# MT29_-_2GBiT_Parallel.net
KiCad netlist of a schematic drawn in Altium Designer
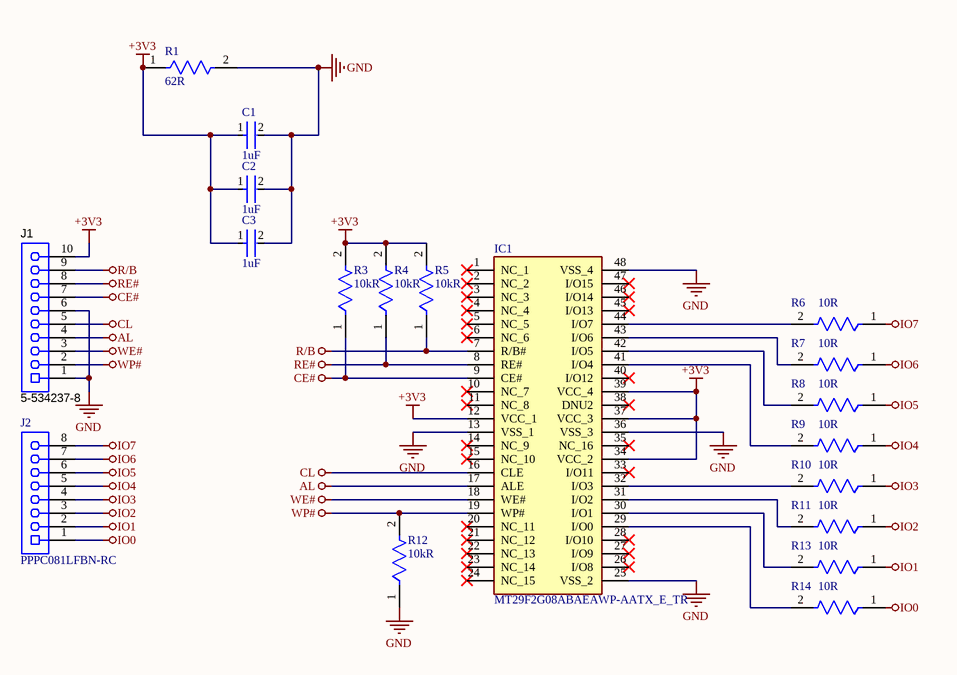
[diagram p0: MT29 - 2GBiT Parallel.SchDoc]

(export (version "E")
  (design (tool "Eeschema 10.0.6"))
  (components
    (comp (ref "C1")
      (value "1uF")
      (footprint "FP-GCM188-0_1-IPC_B")
      (description "Ceramic Capacitor for Automotive 1uF  ±10% 16VDC X7R 0603 Paper T/R")
      (fields (field (name "VOLTAGE") "16V") (field (name "TOLERANCE") "10%"))
      (libsource (lib "Altium Content Vault") (part "02cd4be3c70576c341d710602a673aa"))
    )
    (comp (ref "C2")
      (value "1uF")
      (footprint "FP-GCM188-0_1-IPC_B")
      (description "Ceramic Capacitor for Automotive 1uF  ±10% 16VDC X7R 0603 Paper T/R")
      (fields (field (name "VOLTAGE") "16V") (field (name "TOLERANCE") "10%"))
      (libsource (lib "Altium Content Vault") (part "02cd4be3c70576c341d710602a673aa"))
    )
    (comp (ref "C3")
      (value "1uF")
      (footprint "FP-GCM188-0_1-IPC_B")
      (description "Ceramic Capacitor for Automotive 1uF  ±10% 16VDC X7R 0603 Paper T/R")
      (fields (field (name "VOLTAGE") "16V") (field (name "TOLERANCE") "10%"))
      (libsource (lib "Altium Content Vault") (part "02cd4be3c70576c341d710602a673aa"))
    )
    (comp (ref "IC1")
      (value "MT29F2G08ABAEAWP-AATX_E_TR")
      (footprint "SamacSys:SOP50P2000X120-48N")
      (description "Integrated Circuit")
      (fields
        (field (name "MANUFACTURER_PART_NUMBER") "MT29F2G08ABAEAWP-AATX:E TR")
        (field (name "MOUSER PART NUMBER") "340-278557-REEL")
      )
      (libsource (lib "SamacSys") (part "MT29F2G08ABAEAWP-AATX_E_TR"))
    )
    (comp (ref "J1")
      (value "5-534237-8")
      (footprint "TECO-5-534237-8_V")
      (fields (field (name "MANUFACTURER") "TE Connectivity"))
      (libsource (lib "CubeSat Team") (part "CN-1P-F-R10"))
    )
    (comp (ref "J2")
      (value "PPPC081LFBN-RC")
      (footprint "SLIN-PPPC081LFBN-RC_V")
      (fields (field (name "MANUFACTURER") "Sullins"))
      (libsource (lib "CubeSat Team") (part "CN-1P-F-R8"))
    )
    (comp (ref "R1")
      (value "62R")
      (footprint "FP-AC0603-IPC_A")
      (description "RES 62Ω 1.00% 0.1W 0603")
      (fields (field (name "TOLERANCE") "1%"))
      (libsource (lib "Altium Content Vault") (part "1029c3af85768c4190bb7ad29bc67b5"))
    )
    (comp (ref "R3")
      (value "10kR")
      (footprint "FP-AC0603-IPC_B")
      (description "RES 910KΩ 1.00% 0.1W 0603")
      (fields (field (name "TOLERANCE") "1%"))
      (libsource (lib "Altium Content Vault") (part "1029c3af85768c4190bb7ad29bc67b5"))
    )
    (comp (ref "R4")
      (value "10kR")
      (footprint "FP-AC0603-IPC_B")
      (description "RES 910KΩ 1.00% 0.1W 0603")
      (fields (field (name "TOLERANCE") "1%"))
      (libsource (lib "Altium Content Vault") (part "1029c3af85768c4190bb7ad29bc67b5"))
    )
    (comp (ref "R5")
      (value "10kR")
      (footprint "FP-AC0603-IPC_B")
      (description "RES 910KΩ 1.00% 0.1W 0603")
      (fields (field (name "TOLERANCE") "1%"))
      (libsource (lib "Altium Content Vault") (part "1029c3af85768c4190bb7ad29bc67b5"))
    )
    (comp (ref "R6")
      (value "10R")
      (footprint "FP-AC0603-MFG")
      (description "RES 10Ω 1.00% 0.1W 0603")
      (fields (field (name "TOLERANCE") "1%"))
      (libsource (lib "Altium Content Vault") (part "1029c3af85768c4190bb7ad29bc67b5"))
    )
    (comp (ref "R7")
      (value "10R")
      (footprint "FP-AC0603-MFG")
      (description "RES 10Ω 1.00% 0.1W 0603")
      (fields (field (name "TOLERANCE") "1%"))
      (libsource (lib "Altium Content Vault") (part "1029c3af85768c4190bb7ad29bc67b5"))
    )
    (comp (ref "R8")
      (value "10R")
      (footprint "FP-AC0603-MFG")
      (description "RES 10Ω 1.00% 0.1W 0603")
      (fields (field (name "TOLERANCE") "1%"))
      (libsource (lib "Altium Content Vault") (part "1029c3af85768c4190bb7ad29bc67b5"))
    )
    (comp (ref "R9")
      (value "10R")
      (footprint "FP-AC0603-MFG")
      (description "RES 10Ω 1.00% 0.1W 0603")
      (fields (field (name "TOLERANCE") "1%"))
      (libsource (lib "Altium Content Vault") (part "1029c3af85768c4190bb7ad29bc67b5"))
    )
    (comp (ref "R10")
      (value "10R")
      (footprint "FP-AC0603-MFG")
      (description "RES 10Ω 1.00% 0.1W 0603")
      (fields (field (name "TOLERANCE") "1%"))
      (libsource (lib "Altium Content Vault") (part "1029c3af85768c4190bb7ad29bc67b5"))
    )
    (comp (ref "R11")
      (value "10R")
      (footprint "FP-AC0603-MFG")
      (description "RES 10Ω 1.00% 0.1W 0603")
      (fields (field (name "TOLERANCE") "1%"))
      (libsource (lib "Altium Content Vault") (part "1029c3af85768c4190bb7ad29bc67b5"))
    )
    (comp (ref "R12")
      (value "10kR")
      (footprint "FP-AC0603-IPC_B")
      (description "RES 910KΩ 1.00% 0.1W 0603")
      (fields (field (name "TOLERANCE") "1%"))
      (libsource (lib "Altium Content Vault") (part "1029c3af85768c4190bb7ad29bc67b5"))
    )
    (comp (ref "R13")
      (value "10R")
      (footprint "FP-AC0603-MFG")
      (description "RES 10Ω 1.00% 0.1W 0603")
      (fields (field (name "TOLERANCE") "1%"))
      (libsource (lib "Altium Content Vault") (part "1029c3af85768c4190bb7ad29bc67b5"))
    )
    (comp (ref "R14")
      (value "10R")
      (footprint "FP-AC0603-MFG")
      (description "RES 10Ω 1.00% 0.1W 0603")
      (fields (field (name "TOLERANCE") "1%"))
      (libsource (lib "Altium Content Vault") (part "1029c3af85768c4190bb7ad29bc67b5"))
    )
  )
  (nets
    (net (code "1") (name "+3V3") (class "Default")
      (node (ref "C1") (pin "1") (pinfunction "1_1") (pintype "passive"))
      (node (ref "C2") (pin "1") (pinfunction "1_1") (pintype "passive"))
      (node (ref "C3") (pin "1") (pinfunction "1_1") (pintype "passive"))
      (node (ref "IC1") (pin "12") (pinfunction "VCC_1_12") (pintype "passive"))
      (node (ref "IC1") (pin "34") (pinfunction "VCC_2_34") (pintype "passive"))
      (node (ref "IC1") (pin "37") (pinfunction "VCC_3_37") (pintype "passive"))
      (node (ref "IC1") (pin "39") (pinfunction "VCC_4_39") (pintype "passive"))
      (node (ref "J1") (pin "10") (pinfunction "10_10") (pintype "passive"))
      (node (ref "R1") (pin "1") (pinfunction "1_1") (pintype "passive"))
      (node (ref "R3") (pin "2") (pinfunction "2_2") (pintype "passive"))
      (node (ref "R4") (pin "2") (pinfunction "2_2") (pintype "passive"))
      (node (ref "R5") (pin "2") (pinfunction "2_2") (pintype "passive"))
    )
    (net (code "2") (name "AL") (class "Default")
      (node (ref "IC1") (pin "17") (pinfunction "ALE_17") (pintype "passive"))
      (node (ref "J1") (pin "4") (pinfunction "4_4") (pintype "passive"))
    )
    (net (code "3") (name "CE#") (class "Default")
      (node (ref "IC1") (pin "9") (pinfunction "CE#_9") (pintype "passive"))
      (node (ref "J1") (pin "7") (pinfunction "7_7") (pintype "passive"))
      (node (ref "R3") (pin "1") (pinfunction "1_1") (pintype "passive"))
    )
    (net (code "4") (name "CL") (class "Default")
      (node (ref "IC1") (pin "16") (pinfunction "CLE_16") (pintype "passive"))
      (node (ref "J1") (pin "5") (pinfunction "5_5") (pintype "passive"))
    )
    (net (code "5") (name "GND") (class "Default")
      (node (ref "C1") (pin "2") (pinfunction "2_2") (pintype "passive"))
      (node (ref "C2") (pin "2") (pinfunction "2_2") (pintype "passive"))
      (node (ref "C3") (pin "2") (pinfunction "2_2") (pintype "passive"))
      (node (ref "IC1") (pin "13") (pinfunction "VSS_1_13") (pintype "passive"))
      (node (ref "IC1") (pin "25") (pinfunction "VSS_2_25") (pintype "passive"))
      (node (ref "IC1") (pin "36") (pinfunction "VSS_3_36") (pintype "passive"))
      (node (ref "IC1") (pin "48") (pinfunction "VSS_4_48") (pintype "passive"))
      (node (ref "J1") (pin "1") (pinfunction "1_1") (pintype "passive"))
      (node (ref "J1") (pin "6") (pinfunction "6_6") (pintype "passive"))
      (node (ref "R1") (pin "2") (pinfunction "2_2") (pintype "passive"))
      (node (ref "R12") (pin "1") (pinfunction "1_1") (pintype "passive"))
    )
    (net (code "6") (name "IO0") (class "Default")
      (node (ref "J2") (pin "1") (pinfunction "1_1") (pintype "passive"))
      (node (ref "R14") (pin "1") (pinfunction "1_1") (pintype "passive"))
    )
    (net (code "7") (name "IO1") (class "Default")
      (node (ref "J2") (pin "2") (pinfunction "2_2") (pintype "passive"))
      (node (ref "R13") (pin "1") (pinfunction "1_1") (pintype "passive"))
    )
    (net (code "8") (name "IO2") (class "Default")
      (node (ref "J2") (pin "3") (pinfunction "3_3") (pintype "passive"))
      (node (ref "R11") (pin "1") (pinfunction "1_1") (pintype "passive"))
    )
    (net (code "9") (name "IO3") (class "Default")
      (node (ref "J2") (pin "4") (pinfunction "4_4") (pintype "passive"))
      (node (ref "R10") (pin "1") (pinfunction "1_1") (pintype "passive"))
    )
    (net (code "10") (name "IO4") (class "Default")
      (node (ref "J2") (pin "5") (pinfunction "5_5") (pintype "passive"))
      (node (ref "R9") (pin "1") (pinfunction "1_1") (pintype "passive"))
    )
    (net (code "11") (name "IO5") (class "Default")
      (node (ref "J2") (pin "6") (pinfunction "6_6") (pintype "passive"))
      (node (ref "R8") (pin "1") (pinfunction "1_1") (pintype "passive"))
    )
    (net (code "12") (name "IO6") (class "Default")
      (node (ref "J2") (pin "7") (pinfunction "7_7") (pintype "passive"))
      (node (ref "R7") (pin "1") (pinfunction "1_1") (pintype "passive"))
    )
    (net (code "13") (name "IO7") (class "Default")
      (node (ref "J2") (pin "8") (pinfunction "8_8") (pintype "passive"))
      (node (ref "R6") (pin "1") (pinfunction "1_1") (pintype "passive"))
    )
    (net (code "14") (name "Net-(IC1-I{slash}O0)") (class "Default")
      (node (ref "IC1") (pin "29") (pinfunction "I/O0_29") (pintype "passive"))
      (node (ref "R14") (pin "2") (pinfunction "2_2") (pintype "passive"))
    )
    (net (code "15") (name "Net-(IC1-I{slash}O1)") (class "Default")
      (node (ref "IC1") (pin "30") (pinfunction "I/O1_30") (pintype "passive"))
      (node (ref "R13") (pin "2") (pinfunction "2_2") (pintype "passive"))
    )
    (net (code "16") (name "Net-(IC1-I{slash}O2)") (class "Default")
      (node (ref "IC1") (pin "31") (pinfunction "I/O2_31") (pintype "passive"))
      (node (ref "R11") (pin "2") (pinfunction "2_2") (pintype "passive"))
    )
    (net (code "17") (name "Net-(IC1-I{slash}O3)") (class "Default")
      (node (ref "IC1") (pin "32") (pinfunction "I/O3_32") (pintype "passive"))
      (node (ref "R10") (pin "2") (pinfunction "2_2") (pintype "passive"))
    )
    (net (code "18") (name "Net-(IC1-I{slash}O4)") (class "Default")
      (node (ref "IC1") (pin "41") (pinfunction "I/O4_41") (pintype "passive"))
      (node (ref "R9") (pin "2") (pinfunction "2_2") (pintype "passive"))
    )
    (net (code "19") (name "Net-(IC1-I{slash}O5)") (class "Default")
      (node (ref "IC1") (pin "42") (pinfunction "I/O5_42") (pintype "passive"))
      (node (ref "R8") (pin "2") (pinfunction "2_2") (pintype "passive"))
    )
    (net (code "20") (name "Net-(IC1-I{slash}O6)") (class "Default")
      (node (ref "IC1") (pin "43") (pinfunction "I/O6_43") (pintype "passive"))
      (node (ref "R7") (pin "2") (pinfunction "2_2") (pintype "passive"))
    )
    (net (code "21") (name "Net-(IC1-I{slash}O7)") (class "Default")
      (node (ref "IC1") (pin "44") (pinfunction "I/O7_44") (pintype "passive"))
      (node (ref "R6") (pin "2") (pinfunction "2_2") (pintype "passive"))
    )
    (net (code "22") (name "RE#") (class "Default")
      (node (ref "IC1") (pin "8") (pinfunction "RE#_8") (pintype "passive"))
      (node (ref "J1") (pin "8") (pinfunction "8_8") (pintype "passive"))
      (node (ref "R4") (pin "1") (pinfunction "1_1") (pintype "passive"))
    )
    (net (code "23") (name "R{slash}B") (class "Default")
      (node (ref "IC1") (pin "7") (pinfunction "R/B#_7") (pintype "passive"))
      (node (ref "J1") (pin "9") (pinfunction "9_9") (pintype "passive"))
      (node (ref "R5") (pin "1") (pinfunction "1_1") (pintype "passive"))
    )
    (net (code "24") (name "WE#") (class "Default")
      (node (ref "IC1") (pin "18") (pinfunction "WE#_18") (pintype "passive"))
      (node (ref "J1") (pin "3") (pinfunction "3_3") (pintype "passive"))
    )
    (net (code "25") (name "WP#") (class "Default")
      (node (ref "IC1") (pin "19") (pinfunction "WP#_19") (pintype "passive"))
      (node (ref "J1") (pin "2") (pinfunction "2_2") (pintype "passive"))
      (node (ref "R12") (pin "2") (pinfunction "2_2") (pintype "passive"))
    )
    (net (code "26") (name "unconnected-(IC1-DNU2-Pad38)") (class "Default")
      (node (ref "IC1") (pin "38") (pinfunction "DNU2_38") (pintype "passive+no_connect"))
    )
    (net (code "27") (name "unconnected-(IC1-I{slash}O8-Pad26)") (class "Default")
      (node (ref "IC1") (pin "26") (pinfunction "I/O8_26") (pintype "passive+no_connect"))
    )
    (net (code "28") (name "unconnected-(IC1-I{slash}O9-Pad27)") (class "Default")
      (node (ref "IC1") (pin "27") (pinfunction "I/O9_27") (pintype "passive+no_connect"))
    )
    (net (code "29") (name "unconnected-(IC1-I{slash}O10-Pad28)") (class "Default")
      (node (ref "IC1") (pin "28") (pinfunction "I/O10_28") (pintype "passive+no_connect"))
    )
    (net (code "30") (name "unconnected-(IC1-I{slash}O11-Pad33)") (class "Default")
      (node (ref "IC1") (pin "33") (pinfunction "I/O11_33") (pintype "passive+no_connect"))
    )
    (net (code "31") (name "unconnected-(IC1-I{slash}O12-Pad40)") (class "Default")
      (node (ref "IC1") (pin "40") (pinfunction "I/O12_40") (pintype "passive+no_connect"))
    )
    (net (code "32") (name "unconnected-(IC1-I{slash}O13-Pad45)") (class "Default")
      (node (ref "IC1") (pin "45") (pinfunction "I/O13_45") (pintype "passive+no_connect"))
    )
    (net (code "33") (name "unconnected-(IC1-I{slash}O14-Pad46)") (class "Default")
      (node (ref "IC1") (pin "46") (pinfunction "I/O14_46") (pintype "passive+no_connect"))
    )
    (net (code "34") (name "unconnected-(IC1-I{slash}O15-Pad47)") (class "Default")
      (node (ref "IC1") (pin "47") (pinfunction "I/O15_47") (pintype "passive+no_connect"))
    )
    (net (code "35") (name "unconnected-(IC1-NC_1-Pad1)") (class "Default")
      (node (ref "IC1") (pin "1") (pinfunction "NC_1_1") (pintype "passive+no_connect"))
    )
    (net (code "36") (name "unconnected-(IC1-NC_2-Pad2)") (class "Default")
      (node (ref "IC1") (pin "2") (pinfunction "NC_2_2") (pintype "passive+no_connect"))
    )
    (net (code "37") (name "unconnected-(IC1-NC_3-Pad3)") (class "Default")
      (node (ref "IC1") (pin "3") (pinfunction "NC_3_3") (pintype "passive+no_connect"))
    )
    (net (code "38") (name "unconnected-(IC1-NC_4-Pad4)") (class "Default")
      (node (ref "IC1") (pin "4") (pinfunction "NC_4_4") (pintype "passive+no_connect"))
    )
    (net (code "39") (name "unconnected-(IC1-NC_5-Pad5)") (class "Default")
      (node (ref "IC1") (pin "5") (pinfunction "NC_5_5") (pintype "passive+no_connect"))
    )
    (net (code "40") (name "unconnected-(IC1-NC_6-Pad6)") (class "Default")
      (node (ref "IC1") (pin "6") (pinfunction "NC_6_6") (pintype "passive+no_connect"))
    )
    (net (code "41") (name "unconnected-(IC1-NC_7-Pad10)") (class "Default")
      (node (ref "IC1") (pin "10") (pinfunction "NC_7_10") (pintype "passive+no_connect"))
    )
    (net (code "42") (name "unconnected-(IC1-NC_8-Pad11)") (class "Default")
      (node (ref "IC1") (pin "11") (pinfunction "NC_8_11") (pintype "passive+no_connect"))
    )
    (net (code "43") (name "unconnected-(IC1-NC_9-Pad14)") (class "Default")
      (node (ref "IC1") (pin "14") (pinfunction "NC_9_14") (pintype "passive+no_connect"))
    )
    (net (code "44") (name "unconnected-(IC1-NC_10-Pad15)") (class "Default")
      (node (ref "IC1") (pin "15") (pinfunction "NC_10_15") (pintype "passive+no_connect"))
    )
    (net (code "45") (name "unconnected-(IC1-NC_11-Pad20)") (class "Default")
      (node (ref "IC1") (pin "20") (pinfunction "NC_11_20") (pintype "passive+no_connect"))
    )
    (net (code "46") (name "unconnected-(IC1-NC_12-Pad21)") (class "Default")
      (node (ref "IC1") (pin "21") (pinfunction "NC_12_21") (pintype "passive+no_connect"))
    )
    (net (code "47") (name "unconnected-(IC1-NC_13-Pad22)") (class "Default")
      (node (ref "IC1") (pin "22") (pinfunction "NC_13_22") (pintype "passive+no_connect"))
    )
    (net (code "48") (name "unconnected-(IC1-NC_14-Pad23)") (class "Default")
      (node (ref "IC1") (pin "23") (pinfunction "NC_14_23") (pintype "passive+no_connect"))
    )
    (net (code "49") (name "unconnected-(IC1-NC_15-Pad24)") (class "Default")
      (node (ref "IC1") (pin "24") (pinfunction "NC_15_24") (pintype "passive+no_connect"))
    )
    (net (code "50") (name "unconnected-(IC1-NC_16-Pad35)") (class "Default")
      (node (ref "IC1") (pin "35") (pinfunction "NC_16_35") (pintype "passive+no_connect"))
    )
  )
)
